# host_0.net
KiCad netlist of a schematic drawn in EAGLE
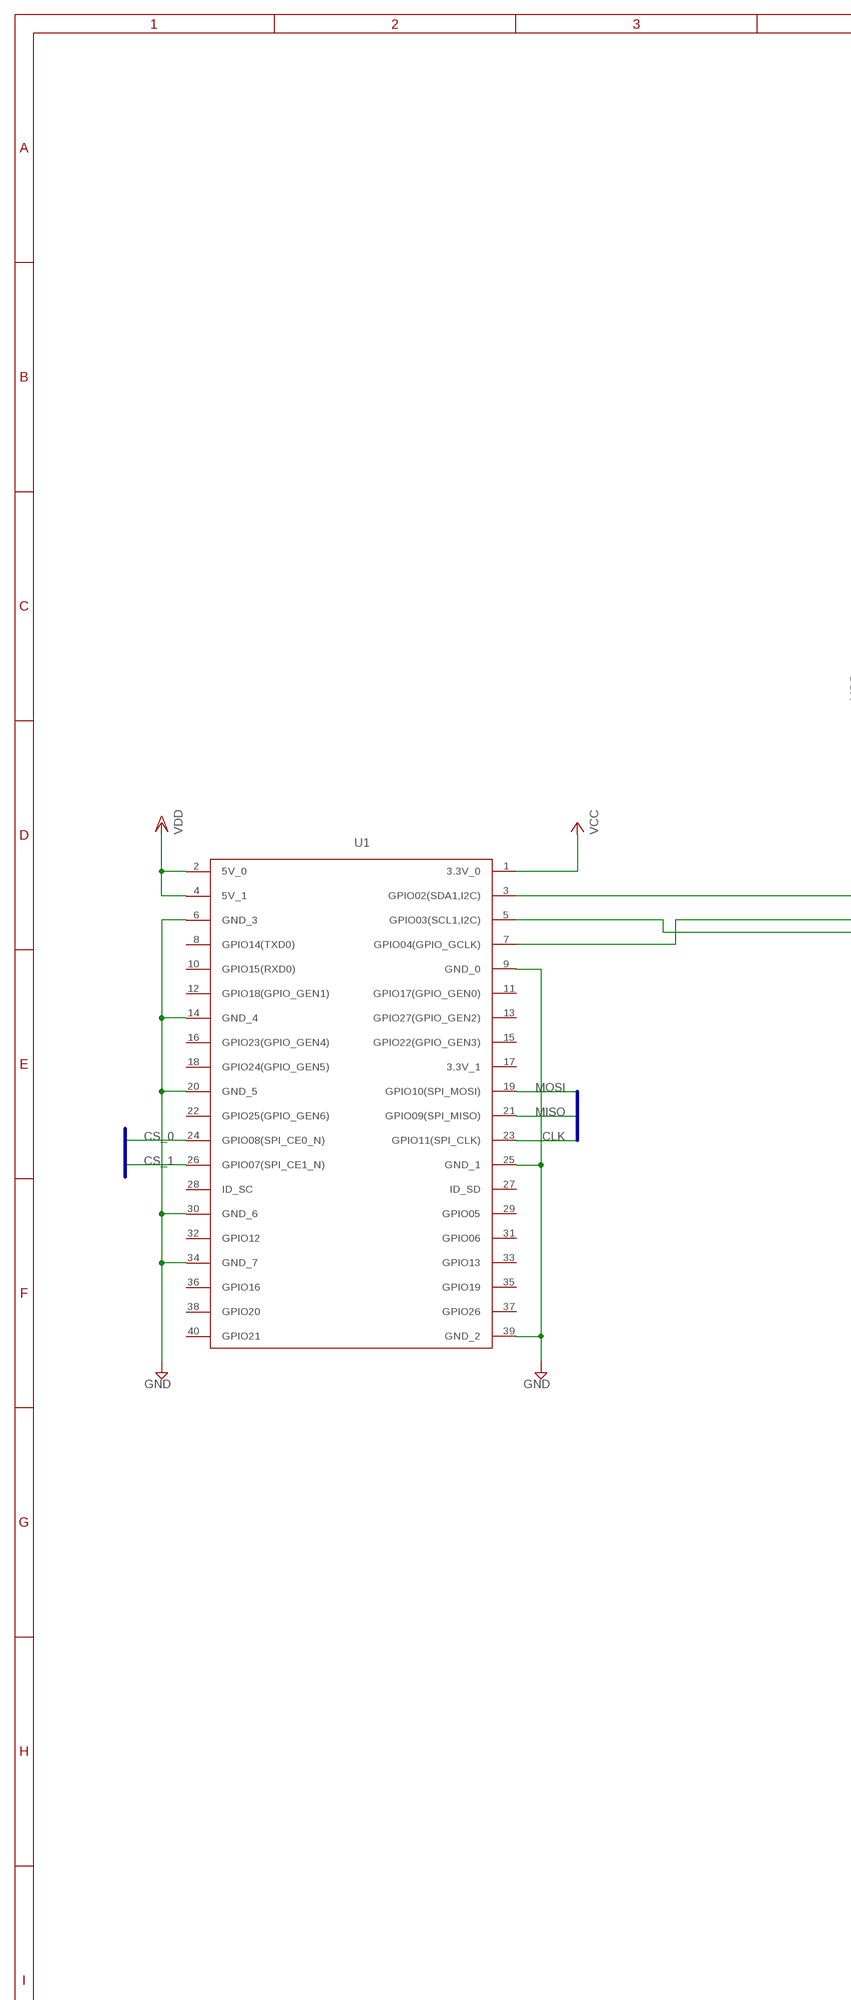
[diagram p0: schematic, sheet 1, part 1 of 2]
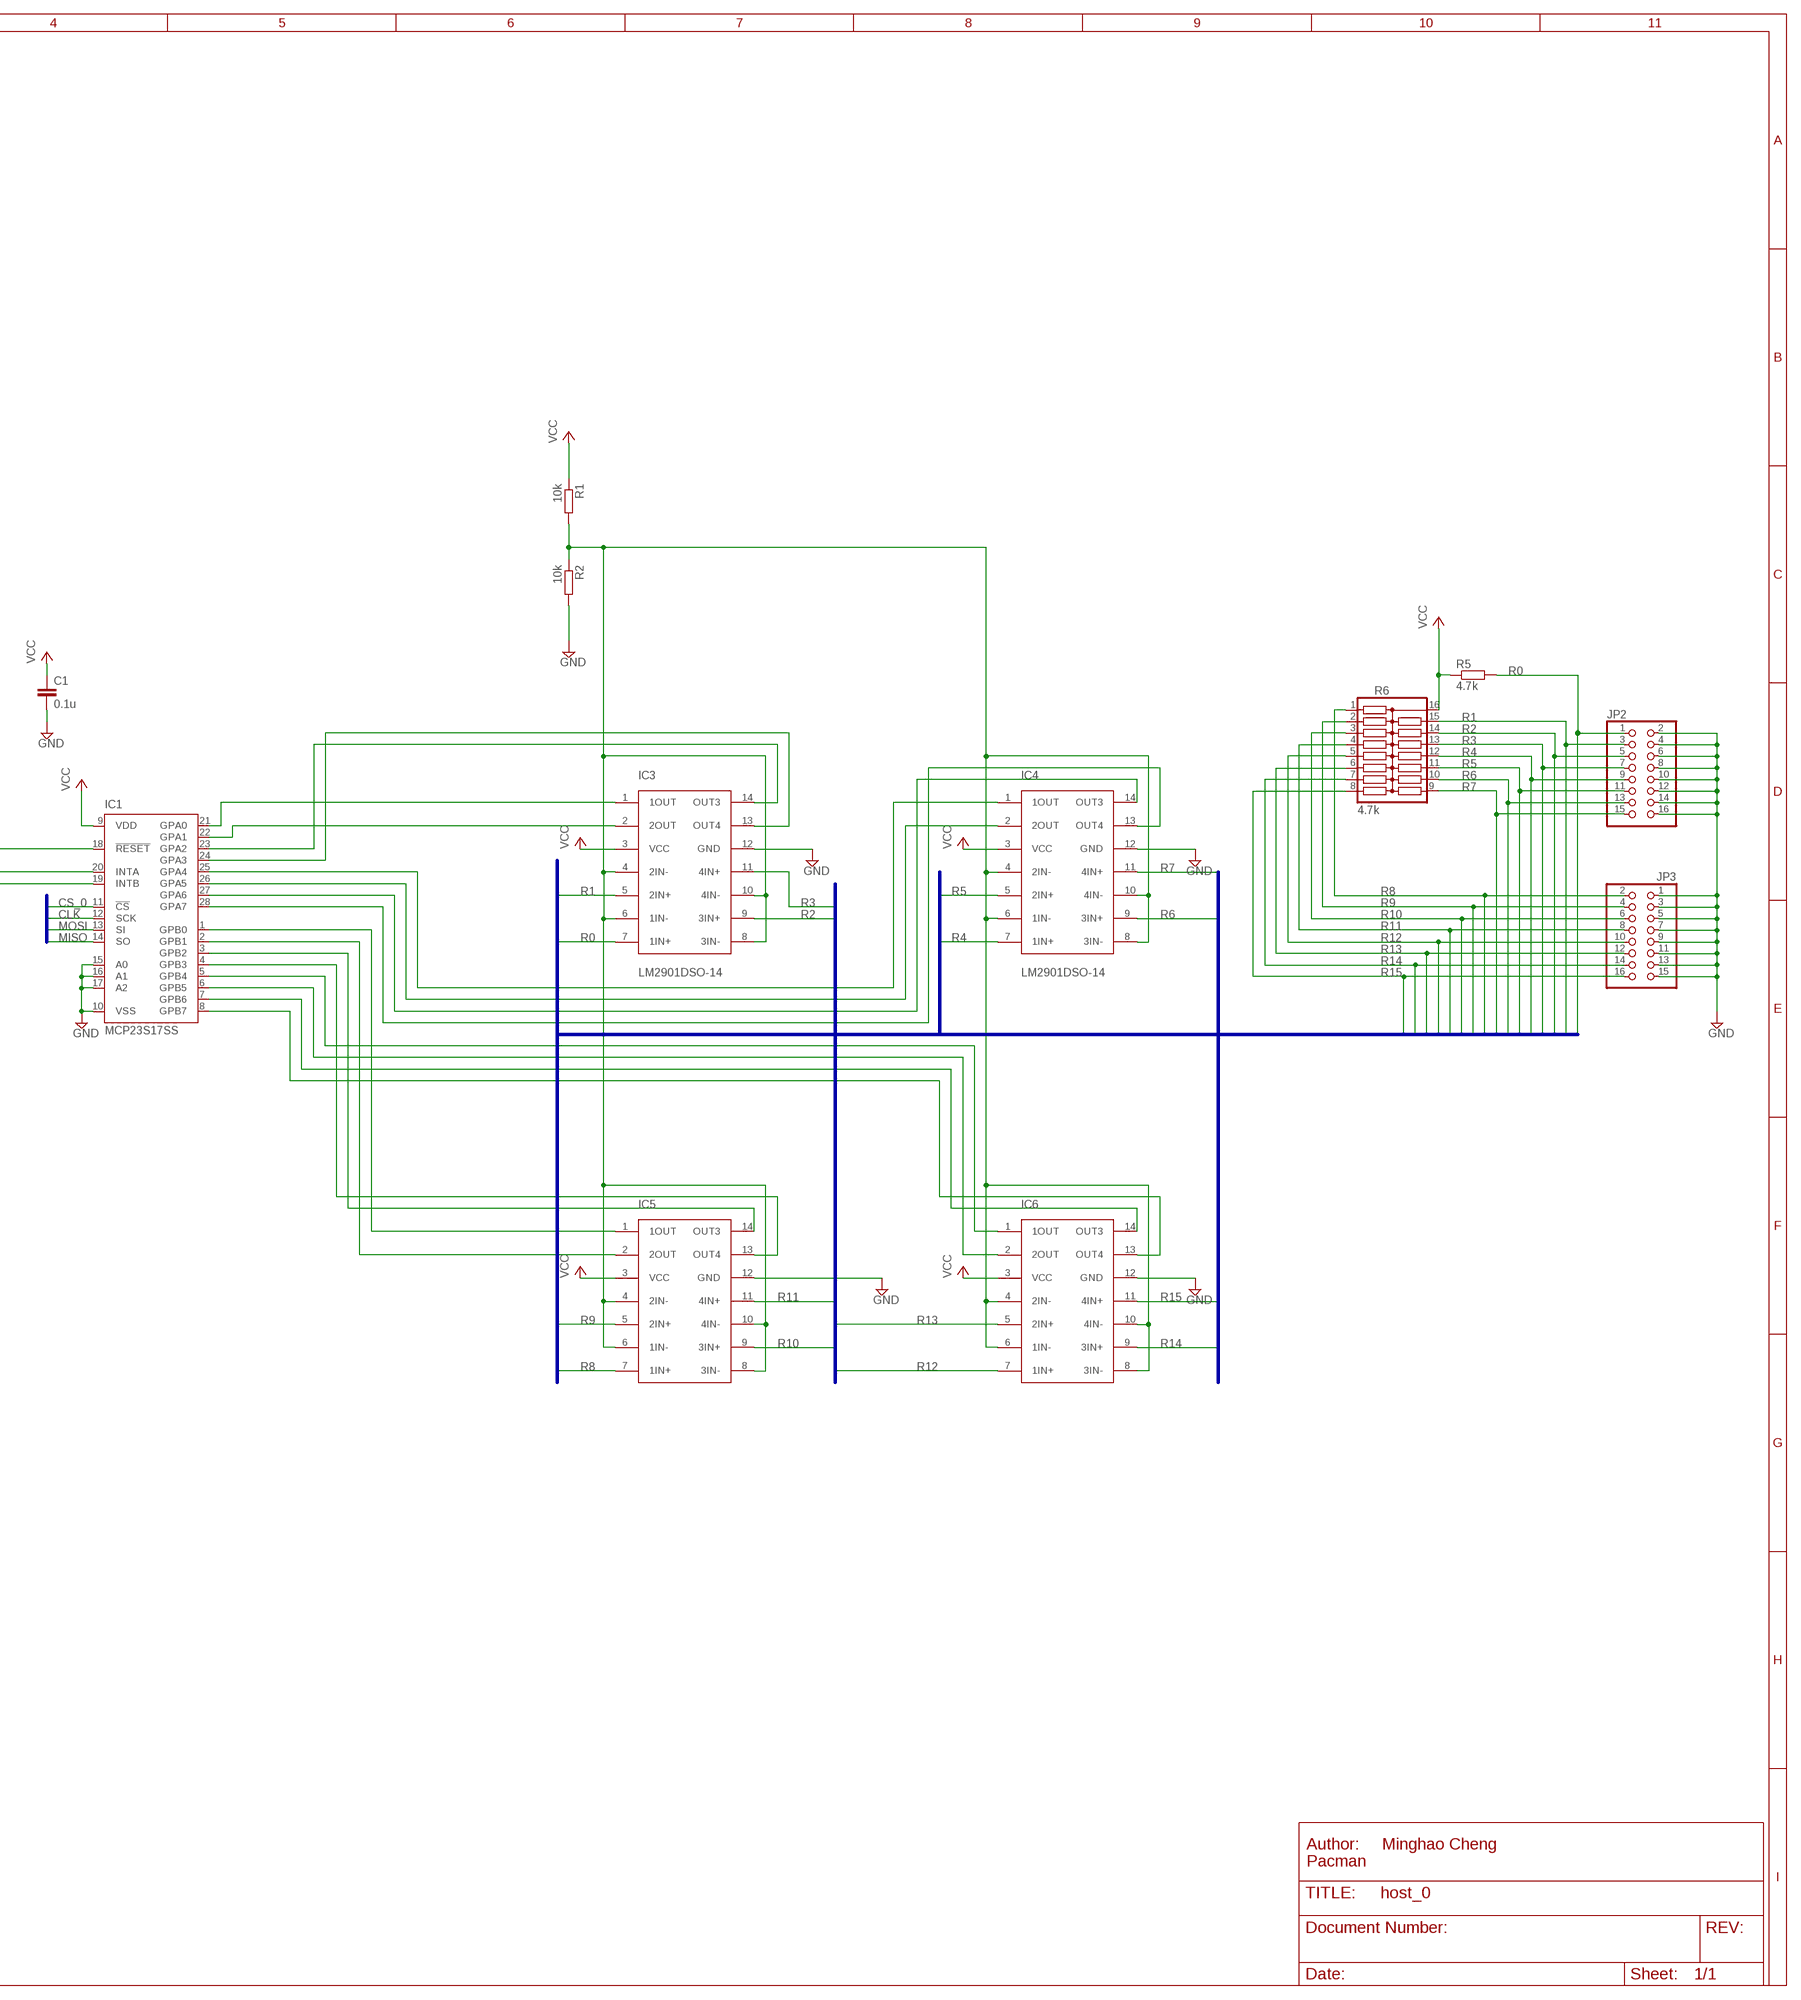
[diagram p1: schematic, sheet 1, part 2 of 2]

(export (version "E")
  (design (tool "Eeschema 10.0.6"))
  (components
    (comp (ref "C1")
      (value "0.1u")
      (footprint "eagle-import:C0805")
      (libsource (lib "eagle-import") (part "C-EUC0805"))
    )
    (comp (ref "IC1")
      (value "MCP23S17SS")
      (footprint "eagle-import:SSOP28")
      (fields (field (name "MF") "MICROCHIP") (field (name "MPN") "MCP23S17-E/SS"))
      (libsource (lib "eagle-import") (part "MCP23S17SS"))
    )
    (comp (ref "IC3")
      (value "LM2901DSO-14")
      (footprint "eagle-import:SO14")
      (libsource (lib "eagle-import") (part "LM2901DSO-14"))
    )
    (comp (ref "IC4")
      (value "LM2901DSO-14")
      (footprint "eagle-import:SO14")
      (libsource (lib "eagle-import") (part "LM2901DSO-14"))
    )
    (comp (ref "IC5")
      (value "LM2901DSO-14")
      (footprint "eagle-import:SO14")
      (libsource (lib "eagle-import") (part "LM2901DSO-14"))
    )
    (comp (ref "IC6")
      (value "LM2901DSO-14")
      (footprint "eagle-import:SO14")
      (libsource (lib "eagle-import") (part "LM2901DSO-14"))
    )
    (comp (ref "JP2")
      (value "PINHD-2X8")
      (footprint "eagle-import:2X08")
      (libsource (lib "eagle-import") (part "PINHD-2X8"))
    )
    (comp (ref "JP3")
      (value "PINHD-2X8")
      (footprint "eagle-import:2X08")
      (libsource (lib "eagle-import") (part "PINHD-2X8"))
    )
    (comp (ref "R1")
      (value "10k")
      (footprint "eagle-import:R0805")
      (libsource (lib "eagle-import") (part "R-EU_R0805"))
    )
    (comp (ref "R2")
      (value "10k")
      (footprint "eagle-import:R0805")
      (libsource (lib "eagle-import") (part "R-EU_R0805"))
    )
    (comp (ref "R5")
      (value "4.7k")
      (footprint "eagle-import:R0805")
      (libsource (lib "eagle-import") (part "R-EU_R0805"))
    )
    (comp (ref "R6")
      (value "4.7k")
      (footprint "eagle-import:4816P")
      (fields (field (name "MF") "BOURNS, INC.") (field (name "MPN") "4816P-T02-824LF"))
      (libsource (lib "eagle-import") (part "4816P-T02"))
    )
    (comp (ref "U1")
      (value "RASPI3_GPIO")
      (footprint "eagle-import:FE20-2")
      (libsource (lib "eagle-import") (part "RASPI3_GPIO"))
    )
  )
  (nets
    (net (code "2") (name "/CLK") (class "Default")
      (node (ref "IC1") (pin "12") (pinfunction "SCK_12") (pintype "input"))
      (node (ref "U1") (pin "23") (pinfunction "GPIO11(SPI_CLK)_23") (pintype "bidirectional"))
    )
    (net (code "3") (name "/CS_0") (class "Default")
      (node (ref "IC1") (pin "11") (pinfunction "~{CS}_11") (pintype "input"))
      (node (ref "U1") (pin "24") (pinfunction "GPIO08(SPI_CE0_N)_24") (pintype "bidirectional"))
    )
    (net (code "4") (name "/CS_1") (class "Default")
      (node (ref "U1") (pin "26") (pinfunction "GPIO07(SPI_CE1_N)_26") (pintype "bidirectional"))
    )
    (net (code "5") (name "/MISO") (class "Default")
      (node (ref "IC1") (pin "14") (pinfunction "SO_14") (pintype "output"))
      (node (ref "U1") (pin "21") (pinfunction "GPIO09(SPI_MISO)_21") (pintype "bidirectional"))
    )
    (net (code "6") (name "/R0") (class "Default")
      (node (ref "IC3") (pin "7") (pinfunction "1IN+_7") (pintype "bidirectional"))
      (node (ref "JP2") (pin "1") (pinfunction "1_1") (pintype "passive"))
      (node (ref "R5") (pin "2") (pinfunction "2_2") (pintype "passive"))
    )
    (net (code "7") (name "/R1") (class "Default")
      (node (ref "IC3") (pin "5") (pinfunction "2IN+_5") (pintype "bidirectional"))
      (node (ref "JP2") (pin "3") (pinfunction "3_3") (pintype "passive"))
      (node (ref "R6") (pin "15") (pinfunction "15_15") (pintype "passive"))
    )
    (net (code "8") (name "/R2") (class "Default")
      (node (ref "IC3") (pin "9") (pinfunction "3IN+_9") (pintype "bidirectional"))
      (node (ref "JP2") (pin "5") (pinfunction "5_5") (pintype "passive"))
      (node (ref "R6") (pin "14") (pinfunction "14_14") (pintype "passive"))
    )
    (net (code "9") (name "/R3") (class "Default")
      (node (ref "IC3") (pin "11") (pinfunction "4IN+_11") (pintype "bidirectional"))
      (node (ref "JP2") (pin "7") (pinfunction "7_7") (pintype "passive"))
      (node (ref "R6") (pin "13") (pinfunction "13_13") (pintype "passive"))
    )
    (net (code "10") (name "/R4") (class "Default")
      (node (ref "IC4") (pin "7") (pinfunction "1IN+_7") (pintype "bidirectional"))
      (node (ref "JP2") (pin "9") (pinfunction "9_9") (pintype "passive"))
      (node (ref "R6") (pin "12") (pinfunction "12_12") (pintype "passive"))
    )
    (net (code "11") (name "/R5") (class "Default")
      (node (ref "IC4") (pin "5") (pinfunction "2IN+_5") (pintype "bidirectional"))
      (node (ref "JP2") (pin "11") (pinfunction "11_11") (pintype "passive"))
      (node (ref "R6") (pin "11") (pinfunction "11_11") (pintype "passive"))
    )
    (net (code "12") (name "/R6") (class "Default")
      (node (ref "IC4") (pin "9") (pinfunction "3IN+_9") (pintype "bidirectional"))
      (node (ref "JP2") (pin "13") (pinfunction "13_13") (pintype "passive"))
      (node (ref "R6") (pin "10") (pinfunction "10_10") (pintype "passive"))
    )
    (net (code "13") (name "/R7") (class "Default")
      (node (ref "IC4") (pin "11") (pinfunction "4IN+_11") (pintype "bidirectional"))
      (node (ref "JP2") (pin "15") (pinfunction "15_15") (pintype "passive"))
      (node (ref "R6") (pin "9") (pinfunction "9_9") (pintype "passive"))
    )
    (net (code "14") (name "/R8") (class "Default")
      (node (ref "IC5") (pin "7") (pinfunction "1IN+_7") (pintype "bidirectional"))
      (node (ref "JP3") (pin "2") (pinfunction "2_2") (pintype "passive"))
      (node (ref "R6") (pin "1") (pinfunction "1_1") (pintype "passive"))
    )
    (net (code "15") (name "/R9") (class "Default")
      (node (ref "IC5") (pin "5") (pinfunction "2IN+_5") (pintype "bidirectional"))
      (node (ref "JP3") (pin "4") (pinfunction "4_4") (pintype "passive"))
      (node (ref "R6") (pin "2") (pinfunction "2_2") (pintype "passive"))
    )
    (net (code "16") (name "/R10") (class "Default")
      (node (ref "IC5") (pin "9") (pinfunction "3IN+_9") (pintype "bidirectional"))
      (node (ref "JP3") (pin "6") (pinfunction "6_6") (pintype "passive"))
      (node (ref "R6") (pin "3") (pinfunction "3_3") (pintype "passive"))
    )
    (net (code "17") (name "/R11") (class "Default")
      (node (ref "IC5") (pin "11") (pinfunction "4IN+_11") (pintype "bidirectional"))
      (node (ref "JP3") (pin "8") (pinfunction "8_8") (pintype "passive"))
      (node (ref "R6") (pin "4") (pinfunction "4_4") (pintype "passive"))
    )
    (net (code "18") (name "/R12") (class "Default")
      (node (ref "IC6") (pin "7") (pinfunction "1IN+_7") (pintype "bidirectional"))
      (node (ref "JP3") (pin "10") (pinfunction "10_10") (pintype "passive"))
      (node (ref "R6") (pin "5") (pinfunction "5_5") (pintype "passive"))
    )
    (net (code "19") (name "/R13") (class "Default")
      (node (ref "IC6") (pin "5") (pinfunction "2IN+_5") (pintype "bidirectional"))
      (node (ref "JP3") (pin "12") (pinfunction "12_12") (pintype "passive"))
      (node (ref "R6") (pin "6") (pinfunction "6_6") (pintype "passive"))
    )
    (net (code "20") (name "/R14") (class "Default")
      (node (ref "IC6") (pin "9") (pinfunction "3IN+_9") (pintype "bidirectional"))
      (node (ref "JP3") (pin "14") (pinfunction "14_14") (pintype "passive"))
      (node (ref "R6") (pin "7") (pinfunction "7_7") (pintype "passive"))
    )
    (net (code "21") (name "/R15") (class "Default")
      (node (ref "IC6") (pin "11") (pinfunction "4IN+_11") (pintype "bidirectional"))
      (node (ref "JP3") (pin "16") (pinfunction "16_16") (pintype "passive"))
      (node (ref "R6") (pin "8") (pinfunction "8_8") (pintype "passive"))
    )
    (net (code "22") (name "/SPI_PI:CLK") (class "Default")
      (node (ref "IC1") (pin "13") (pinfunction "SI_13") (pintype "input"))
      (node (ref "U1") (pin "19") (pinfunction "GPIO10(SPI_MOSI)_19") (pintype "bidirectional"))
    )
    (net (code "24") (name "GND") (class "Default")
      (node (ref "C1") (pin "2") (pinfunction "2_2") (pintype "passive"))
      (node (ref "IC1") (pin "10") (pinfunction "VSS_10") (pintype "power_in"))
      (node (ref "IC1") (pin "15") (pinfunction "A0_15") (pintype "input"))
      (node (ref "IC1") (pin "16") (pinfunction "A1_16") (pintype "input"))
      (node (ref "IC1") (pin "17") (pinfunction "A2_17") (pintype "input"))
      (node (ref "IC3") (pin "12") (pinfunction "GND_12") (pintype "bidirectional"))
      (node (ref "IC4") (pin "12") (pinfunction "GND_12") (pintype "bidirectional"))
      (node (ref "IC5") (pin "12") (pinfunction "GND_12") (pintype "bidirectional"))
      (node (ref "IC6") (pin "12") (pinfunction "GND_12") (pintype "bidirectional"))
      (node (ref "JP2") (pin "10") (pinfunction "10_10") (pintype "passive"))
      (node (ref "JP2") (pin "12") (pinfunction "12_12") (pintype "passive"))
      (node (ref "JP2") (pin "14") (pinfunction "14_14") (pintype "passive"))
      (node (ref "JP2") (pin "16") (pinfunction "16_16") (pintype "passive"))
      (node (ref "JP2") (pin "2") (pinfunction "2_2") (pintype "passive"))
      (node (ref "JP2") (pin "4") (pinfunction "4_4") (pintype "passive"))
      (node (ref "JP2") (pin "6") (pinfunction "6_6") (pintype "passive"))
      (node (ref "JP2") (pin "8") (pinfunction "8_8") (pintype "passive"))
      (node (ref "JP3") (pin "1") (pinfunction "1_1") (pintype "passive"))
      (node (ref "JP3") (pin "11") (pinfunction "11_11") (pintype "passive"))
      (node (ref "JP3") (pin "13") (pinfunction "13_13") (pintype "passive"))
      (node (ref "JP3") (pin "15") (pinfunction "15_15") (pintype "passive"))
      (node (ref "JP3") (pin "3") (pinfunction "3_3") (pintype "passive"))
      (node (ref "JP3") (pin "5") (pinfunction "5_5") (pintype "passive"))
      (node (ref "JP3") (pin "7") (pinfunction "7_7") (pintype "passive"))
      (node (ref "JP3") (pin "9") (pinfunction "9_9") (pintype "passive"))
      (node (ref "R2") (pin "2") (pinfunction "2_2") (pintype "passive"))
      (node (ref "U1") (pin "14") (pinfunction "GND_4_14") (pintype "bidirectional"))
      (node (ref "U1") (pin "20") (pinfunction "GND_5_20") (pintype "bidirectional"))
      (node (ref "U1") (pin "25") (pinfunction "GND_1_25") (pintype "bidirectional"))
      (node (ref "U1") (pin "30") (pinfunction "GND_6_30") (pintype "bidirectional"))
      (node (ref "U1") (pin "34") (pinfunction "GND_7_34") (pintype "bidirectional"))
      (node (ref "U1") (pin "39") (pinfunction "GND_2_39") (pintype "bidirectional"))
      (node (ref "U1") (pin "6") (pinfunction "GND_3_6") (pintype "bidirectional"))
      (node (ref "U1") (pin "9") (pinfunction "GND_0_9") (pintype "bidirectional"))
    )
    (net (code "25") (name "Net-(IC1-GPA0)") (class "Default")
      (node (ref "IC1") (pin "21") (pinfunction "GPA0_21") (pintype "bidirectional"))
      (node (ref "IC3") (pin "1") (pinfunction "1OUT_1") (pintype "bidirectional"))
    )
    (net (code "26") (name "Net-(IC1-GPA1)") (class "Default")
      (node (ref "IC1") (pin "22") (pinfunction "GPA1_22") (pintype "bidirectional"))
      (node (ref "IC3") (pin "2") (pinfunction "2OUT_2") (pintype "bidirectional"))
    )
    (net (code "27") (name "Net-(IC1-GPA2)") (class "Default")
      (node (ref "IC1") (pin "23") (pinfunction "GPA2_23") (pintype "bidirectional"))
      (node (ref "IC3") (pin "14") (pinfunction "OUT3_14") (pintype "bidirectional"))
    )
    (net (code "28") (name "Net-(IC1-GPA3)") (class "Default")
      (node (ref "IC1") (pin "24") (pinfunction "GPA3_24") (pintype "bidirectional"))
      (node (ref "IC3") (pin "13") (pinfunction "OUT4_13") (pintype "bidirectional"))
    )
    (net (code "29") (name "Net-(IC1-GPA4)") (class "Default")
      (node (ref "IC1") (pin "25") (pinfunction "GPA4_25") (pintype "bidirectional"))
      (node (ref "IC4") (pin "1") (pinfunction "1OUT_1") (pintype "bidirectional"))
    )
    (net (code "30") (name "Net-(IC1-GPA5)") (class "Default")
      (node (ref "IC1") (pin "26") (pinfunction "GPA5_26") (pintype "bidirectional"))
      (node (ref "IC4") (pin "2") (pinfunction "2OUT_2") (pintype "bidirectional"))
    )
    (net (code "31") (name "Net-(IC1-GPA6)") (class "Default")
      (node (ref "IC1") (pin "27") (pinfunction "GPA6_27") (pintype "bidirectional"))
      (node (ref "IC4") (pin "14") (pinfunction "OUT3_14") (pintype "bidirectional"))
    )
    (net (code "32") (name "Net-(IC1-GPA7)") (class "Default")
      (node (ref "IC1") (pin "28") (pinfunction "GPA7_28") (pintype "bidirectional"))
      (node (ref "IC4") (pin "13") (pinfunction "OUT4_13") (pintype "bidirectional"))
    )
    (net (code "33") (name "Net-(IC1-GPB0)") (class "Default")
      (node (ref "IC1") (pin "1") (pinfunction "GPB0_1") (pintype "bidirectional"))
      (node (ref "IC5") (pin "1") (pinfunction "1OUT_1") (pintype "bidirectional"))
    )
    (net (code "34") (name "Net-(IC1-GPB1)") (class "Default")
      (node (ref "IC1") (pin "2") (pinfunction "GPB1_2") (pintype "bidirectional"))
      (node (ref "IC5") (pin "2") (pinfunction "2OUT_2") (pintype "bidirectional"))
    )
    (net (code "35") (name "Net-(IC1-GPB2)") (class "Default")
      (node (ref "IC1") (pin "3") (pinfunction "GPB2_3") (pintype "bidirectional"))
      (node (ref "IC5") (pin "14") (pinfunction "OUT3_14") (pintype "bidirectional"))
    )
    (net (code "36") (name "Net-(IC1-GPB3)") (class "Default")
      (node (ref "IC1") (pin "4") (pinfunction "GPB3_4") (pintype "bidirectional"))
      (node (ref "IC5") (pin "13") (pinfunction "OUT4_13") (pintype "bidirectional"))
    )
    (net (code "37") (name "Net-(IC1-GPB4)") (class "Default")
      (node (ref "IC1") (pin "5") (pinfunction "GPB4_5") (pintype "bidirectional"))
      (node (ref "IC6") (pin "1") (pinfunction "1OUT_1") (pintype "bidirectional"))
    )
    (net (code "38") (name "Net-(IC1-GPB5)") (class "Default")
      (node (ref "IC1") (pin "6") (pinfunction "GPB5_6") (pintype "bidirectional"))
      (node (ref "IC6") (pin "2") (pinfunction "2OUT_2") (pintype "bidirectional"))
    )
    (net (code "39") (name "Net-(IC1-GPB6)") (class "Default")
      (node (ref "IC1") (pin "7") (pinfunction "GPB6_7") (pintype "bidirectional"))
      (node (ref "IC6") (pin "14") (pinfunction "OUT3_14") (pintype "bidirectional"))
    )
    (net (code "40") (name "Net-(IC1-GPB7)") (class "Default")
      (node (ref "IC1") (pin "8") (pinfunction "GPB7_8") (pintype "bidirectional"))
      (node (ref "IC6") (pin "13") (pinfunction "OUT4_13") (pintype "bidirectional"))
    )
    (net (code "41") (name "Net-(IC1-INTA)") (class "Default")
      (node (ref "IC1") (pin "20") (pinfunction "INTA_20") (pintype "output"))
      (node (ref "U1") (pin "7") (pinfunction "GPIO04(GPIO_GCLK)_7") (pintype "bidirectional"))
    )
    (net (code "42") (name "Net-(IC1-INTB)") (class "Default")
      (node (ref "IC1") (pin "19") (pinfunction "INTB_19") (pintype "output"))
      (node (ref "U1") (pin "5") (pinfunction "GPIO03(SCL1,I2C)_5") (pintype "bidirectional"))
    )
    (net (code "43") (name "Net-(IC1-~{RESET})") (class "Default")
      (node (ref "IC1") (pin "18") (pinfunction "~{RESET}_18") (pintype "input"))
      (node (ref "U1") (pin "3") (pinfunction "GPIO02(SDA1,I2C)_3") (pintype "bidirectional"))
    )
    (net (code "44") (name "Net-(IC3-1IN-)") (class "Default")
      (node (ref "IC3") (pin "10") (pinfunction "4IN-_10") (pintype "bidirectional"))
      (node (ref "IC3") (pin "4") (pinfunction "2IN-_4") (pintype "bidirectional"))
      (node (ref "IC3") (pin "6") (pinfunction "1IN-_6") (pintype "bidirectional"))
      (node (ref "IC3") (pin "8") (pinfunction "3IN-_8") (pintype "bidirectional"))
      (node (ref "IC4") (pin "10") (pinfunction "4IN-_10") (pintype "bidirectional"))
      (node (ref "IC4") (pin "4") (pinfunction "2IN-_4") (pintype "bidirectional"))
      (node (ref "IC4") (pin "6") (pinfunction "1IN-_6") (pintype "bidirectional"))
      (node (ref "IC4") (pin "8") (pinfunction "3IN-_8") (pintype "bidirectional"))
      (node (ref "IC5") (pin "10") (pinfunction "4IN-_10") (pintype "bidirectional"))
      (node (ref "IC5") (pin "4") (pinfunction "2IN-_4") (pintype "bidirectional"))
      (node (ref "IC5") (pin "6") (pinfunction "1IN-_6") (pintype "bidirectional"))
      (node (ref "IC5") (pin "8") (pinfunction "3IN-_8") (pintype "bidirectional"))
      (node (ref "IC6") (pin "10") (pinfunction "4IN-_10") (pintype "bidirectional"))
      (node (ref "IC6") (pin "4") (pinfunction "2IN-_4") (pintype "bidirectional"))
      (node (ref "IC6") (pin "6") (pinfunction "1IN-_6") (pintype "bidirectional"))
      (node (ref "IC6") (pin "8") (pinfunction "3IN-_8") (pintype "bidirectional"))
      (node (ref "R1") (pin "2") (pinfunction "2_2") (pintype "passive"))
      (node (ref "R2") (pin "1") (pinfunction "1_1") (pintype "passive"))
    )
    (net (code "45") (name "VCC") (class "Default")
      (node (ref "C1") (pin "1") (pinfunction "1_1") (pintype "passive"))
      (node (ref "IC1") (pin "9") (pinfunction "VDD_9") (pintype "power_in"))
      (node (ref "IC3") (pin "3") (pinfunction "VCC_3") (pintype "bidirectional"))
      (node (ref "IC4") (pin "3") (pinfunction "VCC_3") (pintype "bidirectional"))
      (node (ref "IC5") (pin "3") (pinfunction "VCC_3") (pintype "bidirectional"))
      (node (ref "IC6") (pin "3") (pinfunction "VCC_3") (pintype "bidirectional"))
      (node (ref "R1") (pin "1") (pinfunction "1_1") (pintype "passive"))
      (node (ref "R5") (pin "1") (pinfunction "1_1") (pintype "passive"))
      (node (ref "R6") (pin "16") (pinfunction "16_16") (pintype "passive"))
      (node (ref "U1") (pin "1") (pinfunction "3.3V_0_1") (pintype "bidirectional"))
    )
    (net (code "46") (name "VDD") (class "Default")
      (node (ref "U1") (pin "2") (pinfunction "5V_0_2") (pintype "bidirectional"))
      (node (ref "U1") (pin "4") (pinfunction "5V_1_4") (pintype "bidirectional"))
    )
    (net (code "47") (name "unconnected-(U1-3.3V_1-Pad17)") (class "Default")
      (node (ref "U1") (pin "17") (pinfunction "3.3V_1_17") (pintype "bidirectional"))
    )
    (net (code "48") (name "unconnected-(U1-GPIO05-Pad29)") (class "Default")
      (node (ref "U1") (pin "29") (pinfunction "GPIO05_29") (pintype "bidirectional"))
    )
    (net (code "49") (name "unconnected-(U1-GPIO06-Pad31)") (class "Default")
      (node (ref "U1") (pin "31") (pinfunction "GPIO06_31") (pintype "bidirectional"))
    )
    (net (code "50") (name "unconnected-(U1-GPIO12-Pad32)") (class "Default")
      (node (ref "U1") (pin "32") (pinfunction "GPIO12_32") (pintype "bidirectional"))
    )
    (net (code "51") (name "unconnected-(U1-GPIO13-Pad33)") (class "Default")
      (node (ref "U1") (pin "33") (pinfunction "GPIO13_33") (pintype "bidirectional"))
    )
    (net (code "52") (name "unconnected-(U1-GPIO14(TXD0)-Pad8)") (class "Default")
      (node (ref "U1") (pin "8") (pinfunction "GPIO14(TXD0)_8") (pintype "bidirectional"))
    )
    (net (code "53") (name "unconnected-(U1-GPIO15(RXD0)-Pad10)") (class "Default")
      (node (ref "U1") (pin "10") (pinfunction "GPIO15(RXD0)_10") (pintype "bidirectional"))
    )
    (net (code "54") (name "unconnected-(U1-GPIO16-Pad36)") (class "Default")
      (node (ref "U1") (pin "36") (pinfunction "GPIO16_36") (pintype "bidirectional"))
    )
    (net (code "55") (name "unconnected-(U1-GPIO17(GPIO_GEN0)-Pad11)") (class "Default")
      (node (ref "U1") (pin "11") (pinfunction "GPIO17(GPIO_GEN0)_11") (pintype "bidirectional"))
    )
    (net (code "56") (name "unconnected-(U1-GPIO18(GPIO_GEN1)-Pad12)") (class "Default")
      (node (ref "U1") (pin "12") (pinfunction "GPIO18(GPIO_GEN1)_12") (pintype "bidirectional"))
    )
    (net (code "57") (name "unconnected-(U1-GPIO19-Pad35)") (class "Default")
      (node (ref "U1") (pin "35") (pinfunction "GPIO19_35") (pintype "bidirectional"))
    )
    (net (code "58") (name "unconnected-(U1-GPIO20-Pad38)") (class "Default")
      (node (ref "U1") (pin "38") (pinfunction "GPIO20_38") (pintype "bidirectional"))
    )
    (net (code "59") (name "unconnected-(U1-GPIO21-Pad40)") (class "Default")
      (node (ref "U1") (pin "40") (pinfunction "GPIO21_40") (pintype "bidirectional"))
    )
    (net (code "60") (name "unconnected-(U1-GPIO22(GPIO_GEN3)-Pad15)") (class "Default")
      (node (ref "U1") (pin "15") (pinfunction "GPIO22(GPIO_GEN3)_15") (pintype "bidirectional"))
    )
    (net (code "61") (name "unconnected-(U1-GPIO23(GPIO_GEN4)-Pad16)") (class "Default")
      (node (ref "U1") (pin "16") (pinfunction "GPIO23(GPIO_GEN4)_16") (pintype "bidirectional"))
    )
    (net (code "62") (name "unconnected-(U1-GPIO24(GPIO_GEN5)-Pad18)") (class "Default")
      (node (ref "U1") (pin "18") (pinfunction "GPIO24(GPIO_GEN5)_18") (pintype "bidirectional"))
    )
    (net (code "63") (name "unconnected-(U1-GPIO25(GPIO_GEN6)-Pad22)") (class "Default")
      (node (ref "U1") (pin "22") (pinfunction "GPIO25(GPIO_GEN6)_22") (pintype "bidirectional"))
    )
    (net (code "64") (name "unconnected-(U1-GPIO26-Pad37)") (class "Default")
      (node (ref "U1") (pin "37") (pinfunction "GPIO26_37") (pintype "bidirectional"))
    )
    (net (code "65") (name "unconnected-(U1-GPIO27(GPIO_GEN2)-Pad13)") (class "Default")
      (node (ref "U1") (pin "13") (pinfunction "GPIO27(GPIO_GEN2)_13") (pintype "bidirectional"))
    )
    (net (code "66") (name "unconnected-(U1-ID_SC-Pad28)") (class "Default")
      (node (ref "U1") (pin "28") (pinfunction "ID_SC_28") (pintype "bidirectional"))
    )
    (net (code "67") (name "unconnected-(U1-ID_SD-Pad27)") (class "Default")
      (node (ref "U1") (pin "27") (pinfunction "ID_SD_27") (pintype "bidirectional"))
    )
  )
)
